# Voltage_Booster.net
KiCad netlist of a schematic drawn in Altium Designer
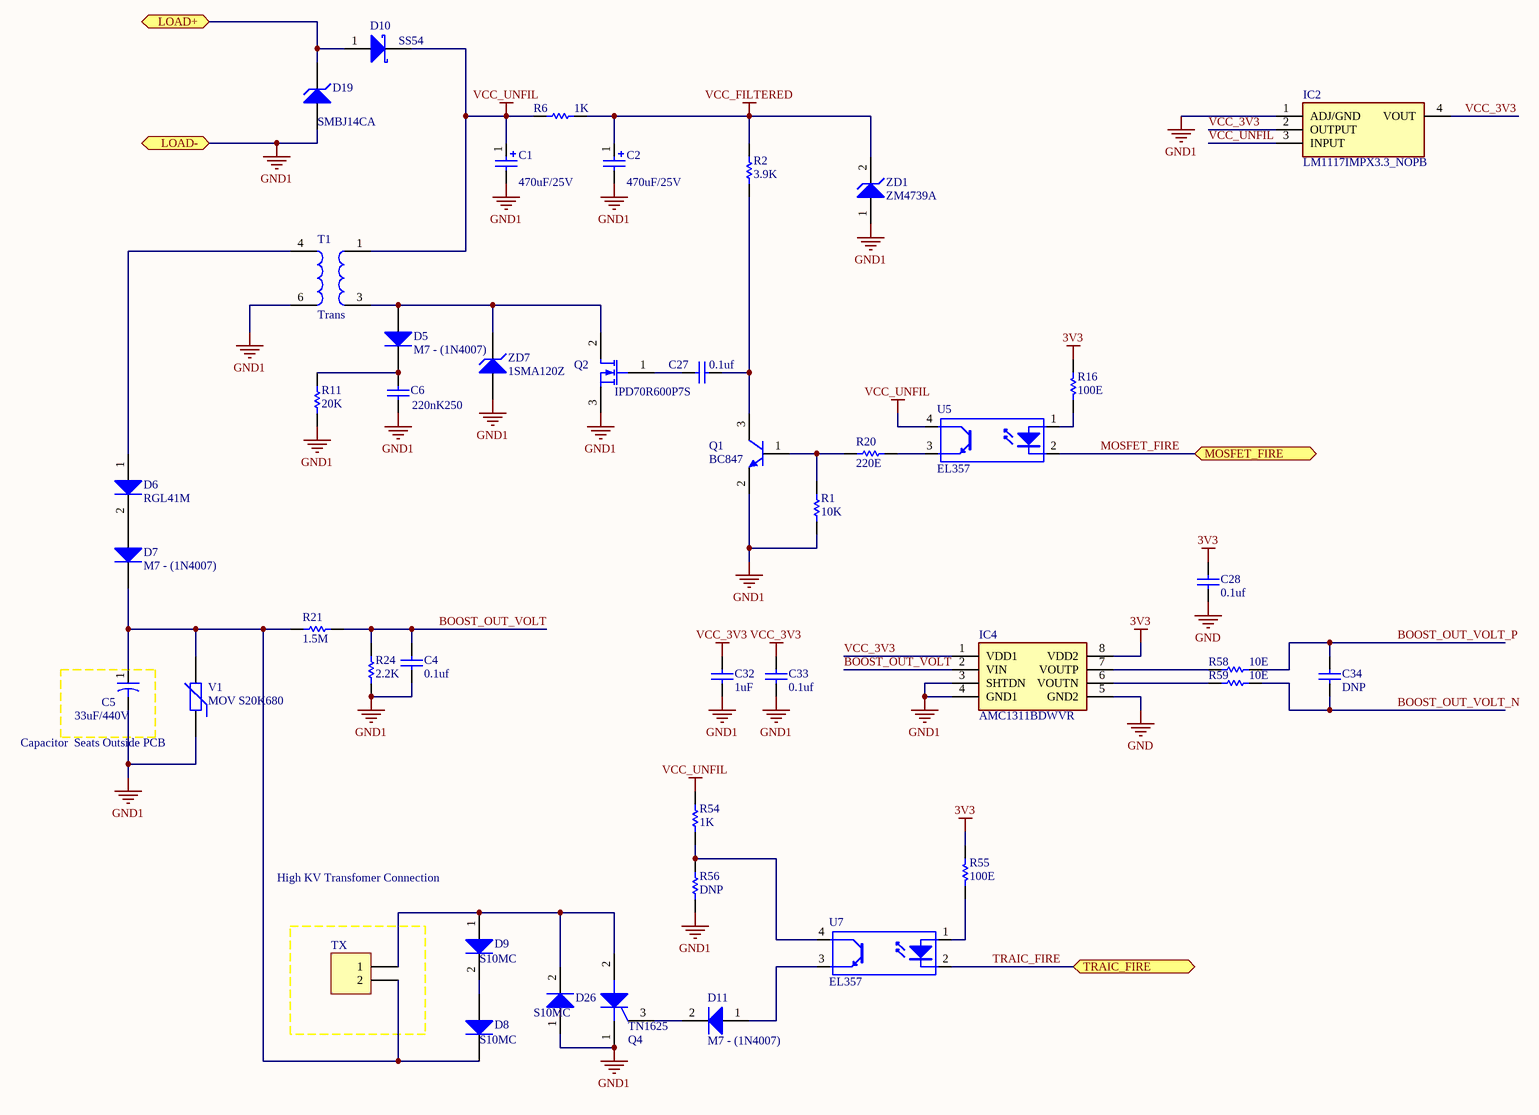
[diagram p0: Voltage_Booster.SchDoc]

(export (version "E")
  (design (tool "Eeschema 10.0.6"))
  (components
    (comp (ref "C1")
      (value "470uF/25V")
      (footprint "Cap_470uf_10X10.2mm")
      (description "Polarized Capacitor (Radial)")
      (fields (field (name "Comment") "Cap Pol1") (field (name "PUBLISHER") "Altium Limited"))
      (libsource (lib "Miscellaneous Devices") (part "Cap Pol1"))
    )
    (comp (ref "C2")
      (value "470uF/25V")
      (footprint "Cap_470uf_10X10.2mm")
      (description "Polarized Capacitor (Radial)")
      (fields (field (name "Comment") "Cap Pol1") (field (name "PUBLISHER") "Altium Limited"))
      (libsource (lib "Miscellaneous Devices") (part "Cap Pol1"))
    )
    (comp (ref "C4")
      (value "0.1uf")
      (footprint "0805")
      (description "Capacitor")
      (fields (field (name "Comment") "Cap") (field (name "PUBLISHER") "Altium Limited"))
      (libsource (lib "Miscellaneous Devices") (part "Cap"))
    )
    (comp (ref "C5")
      (value "33uF/440V")
      (footprint "ENERGIZER_CONNECTOR")
      (description "Capacitor")
      (fields (field (name "Comment") "Cap2") (field (name "PUBLISHER") "Altium Limited"))
      (libsource (lib "Miscellaneous Devices") (part "Cap2"))
    )
    (comp (ref "C6")
      (value "220nK250")
      (footprint "RES AXIAL-0.6")
      (description "Capacitor")
      (fields (field (name "Comment") "Cap") (field (name "PUBLISHER") "Altium Limited"))
      (libsource (lib "Miscellaneous Devices") (part "Cap"))
    )
    (comp (ref "C27")
      (value "0.1uf")
      (footprint "0805")
      (description "Capacitor")
      (fields (field (name "Comment") "Cap") (field (name "PUBLISHER") "Altium Limited"))
      (libsource (lib "Miscellaneous Devices") (part "Cap"))
    )
    (comp (ref "C28")
      (value "0.1uf")
      (footprint "0805")
      (description "Capacitor")
      (fields (field (name "Comment") "Cap") (field (name "PUBLISHER") "Altium Limited"))
      (libsource (lib "Miscellaneous Devices") (part "Cap"))
    )
    (comp (ref "C32")
      (value "1uF")
      (footprint "0805")
      (description "Capacitor")
      (fields (field (name "Comment") "Cap") (field (name "PUBLISHER") "Altium Limited"))
      (libsource (lib "Miscellaneous Devices") (part "Cap"))
    )
    (comp (ref "C33")
      (value "0.1uf")
      (footprint "0805")
      (description "Capacitor")
      (fields (field (name "Comment") "Cap") (field (name "PUBLISHER") "Altium Limited"))
      (libsource (lib "Miscellaneous Devices") (part "Cap"))
    )
    (comp (ref "C34")
      (value "DNP")
      (footprint "0805")
      (description "Capacitor")
      (fields (field (name "Comment") "Cap") (field (name "PUBLISHER") "Altium Limited"))
      (libsource (lib "Miscellaneous Devices") (part "Cap"))
    )
    (comp (ref "D5")
      (value "M7 - (1N4007)")
      (footprint "SMA")
      (description "3 Amp Medium Power Silicon Rectifier Diode")
      (fields (field (name "PUBLISHER") "Altium Limited"))
      (libsource (lib "") (part "Diode 1N5408_1"))
    )
    (comp (ref "D6")
      (value "RGL41M")
      (footprint "DO-213AB")
      (description "3 Amp Medium Power Silicon Rectifier Diode")
      (fields (field (name "PUBLISHER") "Altium Limited"))
      (libsource (lib "Miscellaneous Devices") (part "Diode 1N5408"))
    )
    (comp (ref "D7")
      (value "M7 - (1N4007)")
      (footprint "SMA")
      (description "3 Amp Medium Power Silicon Rectifier Diode")
      (fields (field (name "PUBLISHER") "Altium Limited"))
      (libsource (lib "") (part "Diode 1N5408_1"))
    )
    (comp (ref "D8")
      (value "S10MC")
      (footprint "SMC")
      (description "Default Diode")
      (fields (field (name "PUBLISHER") "Altium Limited"))
      (libsource (lib "") (part "Diode_1"))
    )
    (comp (ref "D9")
      (value "S10MC")
      (footprint "SMC")
      (description "Default Diode")
      (fields (field (name "PUBLISHER") "Altium Limited"))
      (libsource (lib "Miscellaneous Devices") (part "Diode"))
    )
    (comp (ref "D10")
      (value "SS54")
      (footprint "SMC")
      (description "Silicon RF Schottky Diode for Mixer Applications in the VHF/UHF Range")
      (fields (field (name "PUBLISHER") "Altium Limited"))
      (libsource (lib "Miscellaneous Devices") (part "Diode BAT17"))
    )
    (comp (ref "D11")
      (value "M7 - (1N4007)")
      (footprint "SMA")
      (description "1 Amp General Purpose Rectifier")
      (fields (field (name "PUBLISHER") "Altium Limited"))
      (libsource (lib "Miscellaneous Devices") (part "Diode 1N4007"))
    )
    (comp (ref "D19")
      (value "SMBJ14CA")
      (footprint "SMA")
      (description "Zener Diode")
      (fields (field (name "PUBLISHER") "Altium Limited"))
      (libsource (lib "") (part "D Zener_1"))
    )
    (comp (ref "D26")
      (value "S10MC")
      (footprint "SMC")
      (description "Diode P600M")
      (fields (field (name "PUBLISHER") "Altium Limited"))
      (libsource (lib "Miscellaneous Devices") (part "Diode 1N4007"))
    )
    (comp (ref "IC2")
      (value "LM1117IMPX3.3_NOPB")
      (footprint "SOT230P700X180-4N")
      (description "Integrated Circuit")
      (fields (field (name "MANUFACTURER_PART_NUMBER") "LM1117IMPX3.3/NOPB"))
      (libsource (lib "SamacSys") (part "LM1117IMPX3.3_NOPB"))
    )
    (comp (ref "IC4")
      (value "AMC1311BDWVR")
      (footprint "SOIC127P1150X280-8N")
      (description "Integrated Circuit")
      (fields (field (name "MOUSER PART NUMBER") "595-AMC1311BDWVR"))
      (libsource (lib "SamacSys") (part "AMC1311BDWVR"))
    )
    (comp (ref "Q1")
      (value "BC847")
      (footprint "SOT-23")
      (description "NPN General Purpose Amplifier")
      (fields (field (name "PUBLISHER") "Altium Limited"))
      (libsource (lib "Miscellaneous Devices") (part "2N3904"))
    )
    (comp (ref "Q2")
      (value "IPD70R600P7S")
      (footprint "SMDlibrary:TO252 (DPAK)")
      (description "N-Channel MOSFET")
      (fields (field (name "PUBLISHER") "Altium Limited"))
      (libsource (lib "Miscellaneous Devices") (part "MOSFET-N"))
    )
    (comp (ref "Q4")
      (value "TN1625")
      (footprint "SMDlibrary:D2PAK")
      (description "Silicon Controlled Rectifier")
      (fields (field (name "PUBLISHER") "Altium Limited"))
      (libsource (lib "Miscellaneous Devices") (part "SCR"))
    )
    (comp (ref "R1")
      (value "10K")
      (footprint "1206")
      (description "Resistor")
      (fields (field (name "Comment") "Res1") (field (name "PUBLISHER") "Altium Limited"))
      (libsource (lib "Miscellaneous Devices") (part "Res1"))
    )
    (comp (ref "R2")
      (value "3.9K")
      (footprint "1206")
      (description "Resistor")
      (fields (field (name "Comment") "Res1") (field (name "PUBLISHER") "Altium Limited"))
      (libsource (lib "Miscellaneous Devices") (part "Res1"))
    )
    (comp (ref "R6")
      (value "1K")
      (footprint "2512")
      (description "Resistor")
      (fields (field (name "Comment") "Res1") (field (name "PUBLISHER") "Altium Limited"))
      (libsource (lib "Miscellaneous Devices") (part "Res1"))
    )
    (comp (ref "R11")
      (value "20K")
      (footprint "1206")
      (description "Resistor")
      (fields (field (name "Comment") "Res1") (field (name "PUBLISHER") "Altium Limited"))
      (libsource (lib "Miscellaneous Devices") (part "Res1"))
    )
    (comp (ref "R16")
      (value "100E")
      (footprint "0805")
      (description "Resistor")
      (fields (field (name "Comment") "Res1") (field (name "PUBLISHER") "Altium Limited"))
      (libsource (lib "Miscellaneous Devices") (part "Res1"))
    )
    (comp (ref "R20")
      (value "220E")
      (footprint "1206")
      (description "Resistor")
      (fields (field (name "Comment") "Res1") (field (name "PUBLISHER") "Altium Limited"))
      (libsource (lib "Miscellaneous Devices") (part "Res1"))
    )
    (comp (ref "R21")
      (value "1.5M")
      (footprint "1206")
      (description "Resistor")
      (fields (field (name "Comment") "Res1") (field (name "PUBLISHER") "Altium Limited"))
      (libsource (lib "Miscellaneous Devices") (part "Res1"))
    )
    (comp (ref "R24")
      (value "2.2K")
      (footprint "1206")
      (description "Resistor")
      (fields (field (name "Comment") "Res1") (field (name "PUBLISHER") "Altium Limited"))
      (libsource (lib "Miscellaneous Devices") (part "Res1"))
    )
    (comp (ref "R54")
      (value "1K")
      (footprint "1206")
      (description "Resistor")
      (fields (field (name "Comment") "Res1") (field (name "PUBLISHER") "Altium Limited"))
      (libsource (lib "Miscellaneous Devices") (part "Res1"))
    )
    (comp (ref "R55")
      (value "100E")
      (footprint "0805")
      (description "Resistor")
      (fields (field (name "Comment") "Res1") (field (name "PUBLISHER") "Altium Limited"))
      (libsource (lib "Miscellaneous Devices") (part "Res1"))
    )
    (comp (ref "R56")
      (value "DNP")
      (footprint "1206")
      (description "Resistor")
      (fields (field (name "Comment") "Res1") (field (name "PUBLISHER") "Altium Limited"))
      (libsource (lib "Miscellaneous Devices") (part "Res1"))
    )
    (comp (ref "R58")
      (value "10E")
      (footprint "0805")
      (description "Resistor")
      (fields (field (name "Comment") "Res1") (field (name "PUBLISHER") "Altium Limited"))
      (libsource (lib "Miscellaneous Devices") (part "Res1"))
    )
    (comp (ref "R59")
      (value "10E")
      (footprint "0805")
      (description "Resistor")
      (fields (field (name "Comment") "Res1") (field (name "PUBLISHER") "Altium Limited"))
      (libsource (lib "Miscellaneous Devices") (part "Res1"))
    )
    (comp (ref "T1")
      (value "Trans")
      (footprint "TRANSFORMER_ENERGIZER")
      (description "Transformer For Voltage Booster")
      (fields (field (name "PUBLISHER") "Altium Limited"))
      (libsource (lib "Miscellaneous Devices") (part "Trans"))
    )
    (comp (ref "TX")
      (value "High KV Transfomer Connection")
      (footprint "ENERGIZER_CONNECTOR")
      (description "Header, 2-Pin")
      (fields (field (name "PUBLISHER") "Altium Limited"))
      (libsource (lib "Miscellaneous Connectors") (part "Header 2"))
    )
    (comp (ref "U5")
      (value "EL357")
      (footprint "SOP4")
      (description "4-Pin Phototransistor Optocoupler")
      (fields (field (name "PUBLISHER") "Altium Limited"))
      (libsource (lib "Miscellaneous Devices") (part "Optoisolator1"))
    )
    (comp (ref "U7")
      (value "EL357")
      (footprint "SOP4")
      (description "4-Pin Phototransistor Optocoupler")
      (fields (field (name "PUBLISHER") "Altium Limited"))
      (libsource (lib "Miscellaneous Devices") (part "Optoisolator1"))
    )
    (comp (ref "V1")
      (value "MOV S20K680")
      (footprint "3225k471")
      (description "Varistor (Voltage-Sensitive Resistor)")
      (fields (field (name "PUBLISHER") "Altium Limited"))
      (libsource (lib "Miscellaneous Devices") (part "Res Varistor"))
    )
    (comp (ref "ZD1")
      (value "ZM4739A")
      (footprint "SMDlibrary:SMA")
      (description "Zener Diode")
      (fields (field (name "PUBLISHER") "Altium Limited"))
      (libsource (lib "Miscellaneous Devices") (part "D Zener"))
    )
    (comp (ref "ZD7")
      (value "1SMA120Z")
      (footprint "SMA")
      (description "Zener Diode")
      (fields (field (name "PUBLISHER") "Altium Limited"))
      (libsource (lib "") (part "D Zener_1"))
    )
  )
  (nets
    (net (code "1") (name "/BOOST_OUT_VOLT") (class "Default")
      (node (ref "C4") (pin "2") (pinfunction "2_2") (pintype "passive"))
      (node (ref "IC4") (pin "2") (pinfunction "VIN_2") (pintype "passive"))
      (node (ref "R21") (pin "2") (pinfunction "2_2") (pintype "passive"))
      (node (ref "R24") (pin "1") (pinfunction "1_1") (pintype "passive"))
    )
    (net (code "2") (name "/BOOST_OUT_VOLT_N") (class "Default")
      (node (ref "C34") (pin "1") (pinfunction "1_1") (pintype "passive"))
      (node (ref "R59") (pin "2") (pinfunction "2_2") (pintype "passive"))
    )
    (net (code "3") (name "/BOOST_OUT_VOLT_P") (class "Default")
      (node (ref "C34") (pin "2") (pinfunction "2_2") (pintype "passive"))
      (node (ref "R58") (pin "2") (pinfunction "2_2") (pintype "passive"))
    )
    (net (code "4") (name "/LOAD+") (class "Default")
      (node (ref "D10") (pin "1") (pinfunction "A_1") (pintype "passive"))
      (node (ref "D19") (pin "2") (pinfunction "K_2") (pintype "passive"))
    )
    (net (code "5") (name "/MOSFET_FIRE") (class "Default")
      (node (ref "U5") (pin "2") (pinfunction "K_2") (pintype "passive"))
    )
    (net (code "6") (name "/TRAIC_FIRE") (class "Default")
      (node (ref "U7") (pin "2") (pinfunction "K_2") (pintype "passive"))
    )
    (net (code "7") (name "3V3") (class "Default")
      (node (ref "C28") (pin "2") (pinfunction "2_2") (pintype "passive"))
      (node (ref "IC4") (pin "8") (pinfunction "VDD2_8") (pintype "passive"))
      (node (ref "R16") (pin "2") (pinfunction "2_2") (pintype "passive"))
      (node (ref "R55") (pin "2") (pinfunction "2_2") (pintype "passive"))
    )
    (net (code "8") (name "GND") (class "Default")
      (node (ref "C28") (pin "1") (pinfunction "1_1") (pintype "passive"))
      (node (ref "IC4") (pin "5") (pinfunction "GND2_5") (pintype "passive"))
    )
    (net (code "9") (name "GND1") (class "Default")
      (node (ref "C1") (pin "2") (pinfunction "2_2") (pintype "passive"))
      (node (ref "C2") (pin "2") (pinfunction "2_2") (pintype "passive"))
      (node (ref "C32") (pin "1") (pinfunction "1_1") (pintype "passive"))
      (node (ref "C33") (pin "1") (pinfunction "1_1") (pintype "passive"))
      (node (ref "C4") (pin "1") (pinfunction "1_1") (pintype "passive"))
      (node (ref "C5") (pin "2") (pinfunction "2_2") (pintype "passive"))
      (node (ref "C6") (pin "1") (pinfunction "1_1") (pintype "passive"))
      (node (ref "D19") (pin "1") (pinfunction "A_1") (pintype "passive"))
      (node (ref "D26") (pin "1") (pinfunction "A_1") (pintype "passive"))
      (node (ref "IC2") (pin "1") (pinfunction "ADJ/GND_1") (pintype "passive"))
      (node (ref "IC4") (pin "3") (pinfunction "SHTDN_3") (pintype "passive"))
      (node (ref "IC4") (pin "4") (pinfunction "GND1_4") (pintype "passive"))
      (node (ref "Q1") (pin "2") (pinfunction "E_2") (pintype "passive"))
      (node (ref "Q2") (pin "3") (pinfunction "S_3") (pintype "passive"))
      (node (ref "Q4") (pin "1") (pinfunction "K_1") (pintype "passive"))
      (node (ref "R1") (pin "2") (pinfunction "2_2") (pintype "passive"))
      (node (ref "R11") (pin "1") (pinfunction "1_1") (pintype "passive"))
      (node (ref "R24") (pin "2") (pinfunction "2_2") (pintype "passive"))
      (node (ref "R56") (pin "1") (pinfunction "1_1") (pintype "passive"))
      (node (ref "T1") (pin "6") (pinfunction "6_6") (pintype "passive"))
      (node (ref "V1") (pin "1") (pinfunction "1_1") (pintype "passive"))
      (node (ref "ZD1") (pin "1") (pinfunction "A_1") (pintype "passive"))
      (node (ref "ZD7") (pin "1") (pinfunction "A_1") (pintype "passive"))
    )
    (net (code "10") (name "Net-(D5-A)") (class "Default")
      (node (ref "D5") (pin "1") (pinfunction "A_1") (pintype "passive"))
      (node (ref "Q2") (pin "2") (pinfunction "D_2") (pintype "passive"))
      (node (ref "T1") (pin "3") (pinfunction "3_3") (pintype "passive"))
      (node (ref "ZD7") (pin "2") (pinfunction "K_2") (pintype "passive"))
    )
    (net (code "11") (name "Net-(D5-K)") (class "Default")
      (node (ref "C6") (pin "2") (pinfunction "2_2") (pintype "passive"))
      (node (ref "D5") (pin "2") (pinfunction "K_2") (pintype "passive"))
      (node (ref "R11") (pin "2") (pinfunction "2_2") (pintype "passive"))
    )
    (net (code "12") (name "Net-(D6-A)") (class "Default")
      (node (ref "D6") (pin "1") (pinfunction "A_1") (pintype "passive"))
      (node (ref "T1") (pin "4") (pinfunction "4_4") (pintype "passive"))
    )
    (net (code "13") (name "Net-(D6-K)") (class "Default")
      (node (ref "D6") (pin "2") (pinfunction "K_2") (pintype "passive"))
      (node (ref "D7") (pin "1") (pinfunction "A_1") (pintype "passive"))
    )
    (net (code "14") (name "Net-(D7-K)") (class "Default")
      (node (ref "C5") (pin "1") (pinfunction "1_1") (pintype "passive"))
      (node (ref "D7") (pin "2") (pinfunction "K_2") (pintype "passive"))
      (node (ref "D8") (pin "2") (pinfunction "K_2") (pintype "passive"))
      (node (ref "R21") (pin "1") (pinfunction "1_1") (pintype "passive"))
      (node (ref "TX") (pin "2") (pinfunction "2_2") (pintype "passive"))
      (node (ref "V1") (pin "2") (pinfunction "2_2") (pintype "passive"))
    )
    (net (code "15") (name "Net-(D8-A)") (class "Default")
      (node (ref "D8") (pin "1") (pinfunction "A_1") (pintype "passive"))
      (node (ref "D9") (pin "2") (pinfunction "K_2") (pintype "passive"))
    )
    (net (code "16") (name "Net-(D11-A)") (class "Default")
      (node (ref "D11") (pin "1") (pinfunction "A_1") (pintype "passive"))
      (node (ref "U7") (pin "3") (pinfunction "E_3") (pintype "passive"))
    )
    (net (code "17") (name "Net-(D11-K)") (class "Default")
      (node (ref "D11") (pin "2") (pinfunction "K_2") (pintype "passive"))
      (node (ref "Q4") (pin "3") (pinfunction "G_3") (pintype "passive"))
    )
    (net (code "18") (name "Net-(D26-K)") (class "Default")
      (node (ref "D26") (pin "2") (pinfunction "K_2") (pintype "passive"))
      (node (ref "D9") (pin "1") (pinfunction "A_1") (pintype "passive"))
      (node (ref "Q4") (pin "2") (pinfunction "A_2") (pintype "passive"))
      (node (ref "TX") (pin "1") (pinfunction "1_1") (pintype "passive"))
    )
    (net (code "19") (name "Net-(IC4-VOUTN)") (class "Default")
      (node (ref "IC4") (pin "6") (pinfunction "VOUTN_6") (pintype "passive"))
      (node (ref "R59") (pin "1") (pinfunction "1_1") (pintype "passive"))
    )
    (net (code "20") (name "Net-(IC4-VOUTP)") (class "Default")
      (node (ref "IC4") (pin "7") (pinfunction "VOUTP_7") (pintype "passive"))
      (node (ref "R58") (pin "1") (pinfunction "1_1") (pintype "passive"))
    )
    (net (code "21") (name "Net-(Q1-B)") (class "Default")
      (node (ref "Q1") (pin "1") (pinfunction "B_1") (pintype "passive"))
      (node (ref "R1") (pin "1") (pinfunction "1_1") (pintype "passive"))
      (node (ref "R20") (pin "1") (pinfunction "1_1") (pintype "passive"))
    )
    (net (code "22") (name "Net-(Q1-C)") (class "Default")
      (node (ref "C27") (pin "1") (pinfunction "1_1") (pintype "passive"))
      (node (ref "Q1") (pin "3") (pinfunction "C_3") (pintype "passive"))
      (node (ref "R2") (pin "1") (pinfunction "1_1") (pintype "passive"))
    )
    (net (code "23") (name "Net-(Q2-G)") (class "Default")
      (node (ref "C27") (pin "2") (pinfunction "2_2") (pintype "passive"))
      (node (ref "Q2") (pin "1") (pinfunction "G_1") (pintype "passive"))
    )
    (net (code "24") (name "Net-(U5-A)") (class "Default")
      (node (ref "R16") (pin "1") (pinfunction "1_1") (pintype "passive"))
      (node (ref "U5") (pin "1") (pinfunction "A_1") (pintype "passive"))
    )
    (net (code "25") (name "Net-(U5-E)") (class "Default")
      (node (ref "R20") (pin "2") (pinfunction "2_2") (pintype "passive"))
      (node (ref "U5") (pin "3") (pinfunction "E_3") (pintype "passive"))
    )
    (net (code "26") (name "Net-(U7-A)") (class "Default")
      (node (ref "R55") (pin "1") (pinfunction "1_1") (pintype "passive"))
      (node (ref "U7") (pin "1") (pinfunction "A_1") (pintype "passive"))
    )
    (net (code "27") (name "Net-(U7-C)") (class "Default")
      (node (ref "R54") (pin "1") (pinfunction "1_1") (pintype "passive"))
      (node (ref "R56") (pin "2") (pinfunction "2_2") (pintype "passive"))
      (node (ref "U7") (pin "4") (pinfunction "C_4") (pintype "passive"))
    )
    (net (code "28") (name "VCC_3V3") (class "Default")
      (node (ref "C32") (pin "2") (pinfunction "2_2") (pintype "passive"))
      (node (ref "C33") (pin "2") (pinfunction "2_2") (pintype "passive"))
      (node (ref "IC2") (pin "2") (pinfunction "OUTPUT_2") (pintype "passive"))
      (node (ref "IC2") (pin "4") (pinfunction "VOUT_4") (pintype "passive"))
      (node (ref "IC4") (pin "1") (pinfunction "VDD1_1") (pintype "passive"))
    )
    (net (code "29") (name "VCC_FILTERED") (class "Default")
      (node (ref "C2") (pin "1") (pinfunction "1_1") (pintype "passive"))
      (node (ref "R2") (pin "2") (pinfunction "2_2") (pintype "passive"))
      (node (ref "R6") (pin "2") (pinfunction "2_2") (pintype "passive"))
      (node (ref "ZD1") (pin "2") (pinfunction "K_2") (pintype "passive"))
    )
    (net (code "30") (name "VCC_UNFIL") (class "Default")
      (node (ref "C1") (pin "1") (pinfunction "1_1") (pintype "passive"))
      (node (ref "D10") (pin "2") (pinfunction "2_2") (pintype "passive"))
      (node (ref "IC2") (pin "3") (pinfunction "INPUT_3") (pintype "passive"))
      (node (ref "R54") (pin "2") (pinfunction "2_2") (pintype "passive"))
      (node (ref "R6") (pin "1") (pinfunction "1_1") (pintype "passive"))
      (node (ref "T1") (pin "1") (pinfunction "1_1") (pintype "passive"))
      (node (ref "U5") (pin "4") (pinfunction "C_4") (pintype "passive"))
    )
  )
)
